# Main_ETC.net
KiCad netlist of a schematic drawn in Altium Designer
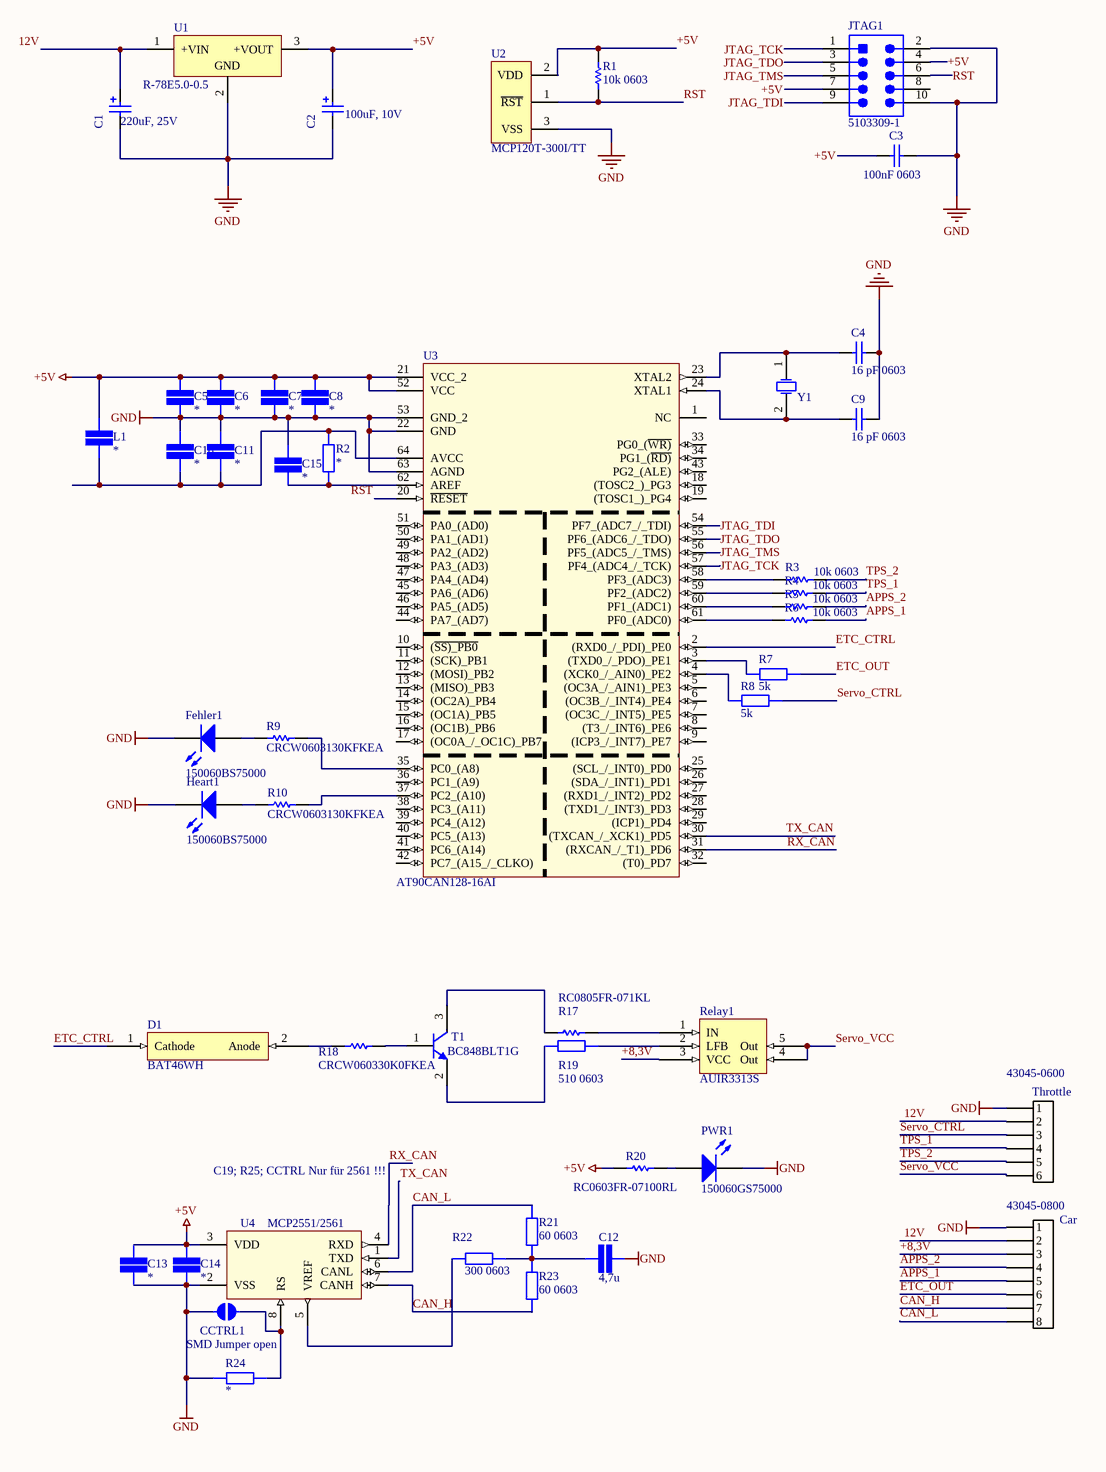
[diagram p0: Main_ETC.SchDoc]

(export (version "E")
  (design (tool "Eeschema 10.0.6"))
  (components
    (comp (ref "C1")
      (value "220uF, 25V")
      (footprint "WCAP-ATET_10x12.5")
      (description "WCAP-ATET THT Aluminum Electrolytic Capacitors, D10mm x L12.5mm, 220uF, +/-20%, 25VDC")
      (fields (field (name "PART NUMBER") "860130475006") (field (name "PUBLISHER") "Wurth Elektronik"))
      (libsource (lib "Altium_WCAP-ATET (rev19a)") (part "860130475006"))
    )
    (comp (ref "C2")
      (value "100uF, 10V")
      (footprint "WCAP-ASLU_6.3x7.7")
      (description "WCAP-ASLU Aluminium Electrolytic Capacitors, D6.3mm x L7.7mm, 100uF, +/-20%, 10VDC")
      (fields (field (name "PART NUMBER") "865090245005") (field (name "PUBLISHER") "Wurth Elektronik"))
      (libsource (lib "Altium_WCAP-ASLU (rev19a)") (part "865090245005"))
    )
    (comp (ref "C3")
      (value "100nF 0603")
      (footprint "CAPC0603(1608)100_L")
      (description "CAP 100nF 10V ±5% 0603 (1608 Metric) Thickness 1mm SMD")
      (fields (field (name "TOLERANCE") "Â±5%"))
      (libsource (lib "Altium Content Vault") (part "CAP"))
    )
    (comp (ref "C4")
      (value "16 pF 0603")
      (footprint "CAPC0603(1608)100_L")
      (description "CAP 100nF 10V ±5% 0603 (1608 Metric) Thickness 1mm SMD")
      (fields (field (name "TOLERANCE") "Â±5%"))
      (libsource (lib "Altium Content Vault") (part "CAP"))
    )
    (comp (ref "C5")
      (value "SMD Capacitor")
      (footprint "CAP 0603/1608")
      (description "Capacitor with multiple Footprints")
      (fields (field (name "ALTIUM_VALUE") "*"))
      (libsource (lib "Standardbauteile") (part "SMD Capacitor"))
    )
    (comp (ref "C6")
      (value "SMD Capacitor")
      (footprint "CAP 0603/1608")
      (description "Capacitor with multiple Footprints")
      (fields (field (name "ALTIUM_VALUE") "*"))
      (libsource (lib "Standardbauteile") (part "SMD Capacitor"))
    )
    (comp (ref "C7")
      (value "SMD Capacitor")
      (footprint "CAP 0603/1608")
      (description "Capacitor with multiple Footprints")
      (fields (field (name "ALTIUM_VALUE") "*"))
      (libsource (lib "Standardbauteile") (part "SMD Capacitor"))
    )
    (comp (ref "C8")
      (value "SMD Capacitor")
      (footprint "CAP 0603/1608")
      (description "Capacitor with multiple Footprints")
      (fields (field (name "ALTIUM_VALUE") "*"))
      (libsource (lib "Standardbauteile") (part "SMD Capacitor"))
    )
    (comp (ref "C9")
      (value "16 pF 0603")
      (footprint "CAPC0603(1608)100_L")
      (description "CAP 100nF 10V ±5% 0603 (1608 Metric) Thickness 1mm SMD")
      (fields (field (name "TOLERANCE") "Â±5%"))
      (libsource (lib "Altium Content Vault") (part "CAP"))
    )
    (comp (ref "C10")
      (value "SMD Capacitor")
      (footprint "CAP 0603/1608")
      (description "Capacitor with multiple Footprints")
      (fields (field (name "ALTIUM_VALUE") "*"))
      (libsource (lib "Standardbauteile") (part "SMD Capacitor"))
    )
    (comp (ref "C11")
      (value "SMD Capacitor")
      (footprint "CAP 0603/1608")
      (description "Capacitor with multiple Footprints")
      (fields (field (name "ALTIUM_VALUE") "*"))
      (libsource (lib "Standardbauteile") (part "SMD Capacitor"))
    )
    (comp (ref "C12")
      (value "4,7u")
      (footprint "CAP 0603/1608")
      (description "Capacitor with multiple Footprints")
      (fields (field (name "Comment") "SMD Capacitor"))
      (libsource (lib "") (part "SMD Capacitor_1"))
    )
    (comp (ref "C13")
      (value "SMD Capacitor")
      (footprint "CAP 0603/1608")
      (description "Capacitor with multiple Footprints")
      (fields (field (name "ALTIUM_VALUE") "*"))
      (libsource (lib "Standardbauteile") (part "SMD Capacitor"))
    )
    (comp (ref "C14")
      (value "SMD Capacitor")
      (footprint "CAP 0603/1608")
      (description "Capacitor with multiple Footprints")
      (fields (field (name "ALTIUM_VALUE") "*"))
      (libsource (lib "Standardbauteile") (part "SMD Capacitor"))
    )
    (comp (ref "C15")
      (value "SMD Capacitor")
      (footprint "CAP 0603/1608")
      (description "Capacitor with multiple Footprints")
      (fields (field (name "ALTIUM_VALUE") "*"))
      (libsource (lib "Standardbauteile") (part "SMD Capacitor"))
    )
    (comp (ref "Car")
      (value "43045-0800")
      (footprint "43045-0800")
      (description "Molex Micro-Fit 3.0 8-Pin\r\n600V\r\n8.5A")
      (libsource (lib "Standardbauteile") (part "MicroFit3.0 8-Pin"))
    )
    (comp (ref "CCTRL1")
      (value "SMD Jumper open")
      (footprint "SMD-JUMPER-OPEN")
      (libsource (lib "Standardbauteile") (part "SMD Jumper open"))
    )
    (comp (ref "D1")
      (value "BAT46WH")
      (footprint "DIOM2715X18N")
      (libsource (lib "Integrated_LibraryLukas") (part "BAT46WH"))
    )
    (comp (ref "Fehler1")
      (value "150060BS75000")
      (footprint "0603_A")
      (description "SMD mono-color Chip LED, WL-SMCW, Blue")
      (fields (field (name "MANUFACTURER") "Wuerth Elektronik"))
      (libsource (lib "Altium Content Vault") (part "WE-LED_K1A2-2"))
    )
    (comp (ref "Heart1")
      (value "150060BS75000")
      (footprint "0603_A")
      (description "SMD mono-color Chip LED, WL-SMCW, Blue")
      (fields (field (name "MANUFACTURER") "Wuerth Elektronik"))
      (libsource (lib "Altium Content Vault") (part "WE-LED_K1A2-2"))
    )
    (comp (ref "JTAG1")
      (value "5103309-1")
      (footprint "TECO-5103309-1_V")
      (fields (field (name "MANUFACTURER") "TE Connectivity"))
      (libsource (lib "Altium Content Vault") (part "CN-2P-M-R10"))
    )
    (comp (ref "L1")
      (value "SMD Capacitor")
      (footprint "CAP 0603/1608")
      (description "Capacitor with multiple Footprints")
      (fields (field (name "ALTIUM_VALUE") "*"))
      (libsource (lib "Standardbauteile") (part "SMD Capacitor"))
    )
    (comp (ref "PWR1")
      (value "150060GS75000")
      (footprint "0603_A")
      (description "SMD mono-color Chip LED, WL-SMCW, Green")
      (fields (field (name "MANUFACTURER") "Wuerth Elektronik"))
      (libsource (lib "Altium Content Vault") (part "WE-LED_K1A2-2"))
    )
    (comp (ref "R1")
      (value "10k 0603")
      (footprint "RESC0603(1608)_N")
      (description "127R 0.1W 1% 0603 (1608 Metric)  SMD")
      (fields (field (name "POWER") "0.1 W") (field (name "TOLERANCE") "1 %"))
      (libsource (lib "Altium Content Vault") (part "RES"))
    )
    (comp (ref "R2")
      (value "SMD Resistor")
      (footprint "STACKPOLE CSR0603")
      (description "Resistor with multiple footprints")
      (fields (field (name "ALTIUM_VALUE") "*"))
      (libsource (lib "Standardbauteile") (part "SMD Resistor"))
    )
    (comp (ref "R3")
      (value "10k 0603")
      (footprint "RESC0603(1608)_N")
      (description "127R 0.1W 1% 0603 (1608 Metric)  SMD")
      (fields (field (name "POWER") "0.1 W") (field (name "TOLERANCE") "1 %"))
      (libsource (lib "Altium Content Vault") (part "RES"))
    )
    (comp (ref "R4")
      (value "10k 0603")
      (footprint "RESC0603(1608)_N")
      (description "127R 0.1W 1% 0603 (1608 Metric)  SMD")
      (fields (field (name "POWER") "0.1 W") (field (name "TOLERANCE") "1 %"))
      (libsource (lib "Altium Content Vault") (part "RES"))
    )
    (comp (ref "R5")
      (value "10k 0603")
      (footprint "RESC0603(1608)_N")
      (description "127R 0.1W 1% 0603 (1608 Metric)  SMD")
      (fields (field (name "POWER") "0.1 W") (field (name "TOLERANCE") "1 %"))
      (libsource (lib "Altium Content Vault") (part "RES"))
    )
    (comp (ref "R6")
      (value "10k 0603")
      (footprint "RESC0603(1608)_N")
      (description "127R 0.1W 1% 0603 (1608 Metric)  SMD")
      (fields (field (name "POWER") "0.1 W") (field (name "TOLERANCE") "1 %"))
      (libsource (lib "Altium Content Vault") (part "RES"))
    )
    (comp (ref "R7")
      (value "5k")
      (footprint "STACKPOLE CSR0603")
      (description "Resistor with multiple footprints")
      (fields (field (name "Comment") "SMD Resistor"))
      (libsource (lib "Standardbauteile") (part "SMD Resistor"))
    )
    (comp (ref "R8")
      (value "5k")
      (footprint "STACKPOLE CSR0603")
      (description "Resistor with multiple footprints")
      (fields (field (name "Comment") "SMD Resistor"))
      (libsource (lib "Standardbauteile") (part "SMD Resistor"))
    )
    (comp (ref "R9")
      (value "CRCW0603130KFKEA")
      (footprint "RESC1609X50X30NL10T20")
      (fields (field (name "MANUFACTURER") "Vishay Dale"))
      (libsource (lib "Altium Content Vault") (part "RES"))
    )
    (comp (ref "R10")
      (value "CRCW0603130KFKEA")
      (footprint "RESC1609X50X30NL10T20")
      (fields (field (name "MANUFACTURER") "Vishay Dale"))
      (libsource (lib "Altium Content Vault") (part "RES"))
    )
    (comp (ref "R17")
      (value "RC0805FR-071KL")
      (footprint "RESC2013X60X35ML10T20")
      (description "Chip Resistor, 1 KOhm, +/- 1%, 125 mW, -55 to 155 degC, 0805 (2012 Metric), RoHS, Tape and Reel")
      (fields (field (name "TOLERANCE") "1%") (field (name "MANUFACTURER") "Yageo"))
      (libsource (lib "Altium Content Vault") (part "RES-2"))
    )
    (comp (ref "R18")
      (value "CRCW060330K0FKEA")
      (footprint "RESC1609X50X30LL10T20")
      (fields (field (name "MANUFACTURER") "Vishay Dale"))
      (libsource (lib "Altium Content Vault") (part "RES"))
    )
    (comp (ref "R19")
      (value "510 0603")
      (footprint "STACKPOLE CSR0603")
      (description "Resistor with multiple footprints")
      (fields (field (name "Comment") "SMD Resistor"))
      (libsource (lib "Standardbauteile") (part "SMD Resistor"))
    )
    (comp (ref "R20")
      (value "RC0603FR-07100RL")
      (footprint "RESC1608X55X25ML10T15")
      (description "Chip Resistor, 100 Ohm, +/- 1%, 0.1 W, -55 to 155 degC, 0603 (1608 Metric), RoHS, Tape and Reel")
      (fields (field (name "TOLERANCE") "1%") (field (name "MANUFACTURER") "Yageo"))
      (libsource (lib "Altium Content Vault") (part "RES-2"))
    )
    (comp (ref "R21")
      (value "60 0603")
      (footprint "STACKPOLE CSR0603")
      (description "Resistor with multiple footprints")
      (fields (field (name "Comment") "SMD Resistor"))
      (libsource (lib "Standardbauteile") (part "SMD Resistor"))
    )
    (comp (ref "R22")
      (value "300 0603")
      (footprint "STACKPOLE CSR0603")
      (description "Resistor with multiple footprints")
      (fields (field (name "Comment") "SMD Resistor"))
      (libsource (lib "Standardbauteile") (part "SMD Resistor"))
    )
    (comp (ref "R23")
      (value "60 0603")
      (footprint "STACKPOLE CSR0603")
      (description "Resistor with multiple footprints")
      (fields (field (name "Comment") "SMD Resistor"))
      (libsource (lib "Standardbauteile") (part "SMD Resistor"))
    )
    (comp (ref "R24")
      (value "SMD Resistor")
      (footprint "STACKPOLE CSR0603")
      (description "Resistor with multiple footprints")
      (fields (field (name "ALTIUM_VALUE") "*"))
      (libsource (lib "Standardbauteile") (part "SMD Resistor"))
    )
    (comp (ref "Relay1")
      (value "AUIR3313S")
      (footprint "D2PAK5 ;DPAK228P1524X483-5N")
      (libsource (lib "Integrated_LibraryLukas") (part "AUIR3313S"))
    )
    (comp (ref "T1")
      (value "BC848BLT1G")
      (footprint "ONSC-SOT-23-3-318-08_V")
      (description "General Purpose Transistor, NPN Silicon, 3-Pin SOT-23, Pb-Free, Tape and Reel")
      (fields (field (name "MANUFACTURER") "On Semiconductor"))
      (libsource (lib "Altium Content Vault") (part "ONSC-NPN-B1E2C3-3"))
    )
    (comp (ref "Throttle")
      (value "43045-0600")
      (footprint "43045-0600")
      (description "Molex Micro-Fit 3.0 6-Pin\r\n600V\r\n8.5A")
      (libsource (lib "Standardbauteile") (part "MicroFit3.0 6-Pin"))
    )
    (comp (ref "U1")
      (value "R-78E5.0-0.5")
      (footprint "REPO-R-78E-0.5-3_V")
      (description "DC/DC-Converter, 5 V Single Output, 500 mA, -40 to 85 degC, 3-Pin THD, RoHS, Tube")
      (fields (field (name "MANUFACTURER") "Recom Power"))
      (libsource (lib "Altium Content Vault") (part "REPO-R-78XX-3"))
    )
    (comp (ref "U2")
      (value "MCP120T-300I/TT")
      (footprint "SOT-23-TT3_N")
      (libsource (lib "Altium Content Vault") (part "PM-SCCT-MCP120-3"))
    )
    (comp (ref "U3")
      (value "AT90CAN128-16AI")
      (footprint "*QFP80P1600X1600X120-64N")
      (description "Ic Mcu 8bit 128kb Flash 64tqfp")
      (fields (field (name "MF") "Microchip"))
      (libsource (lib "Eric") (part "AT90CAN128-16AI"))
    )
    (comp (ref "U4")
      (value "MCP2551/2561")
      (footprint "*SOIC127P600X175-8N")
      (description "MCP2551 Series 5.5 V 1 Mb/s Surface Mount High-Speed CAN Transceiver - SOIC-8")
      (fields (field (name "MP") "MCP2551-I/SN") (field (name "MF") "Microchip"))
      (libsource (lib "Eric") (part "MCP2551-I/SN"))
    )
    (comp (ref "Y1")
      (value "16MHz, +/-30ppm, 16pF")
      (footprint "WE-XTAL_HC49/4HSMX")
      (description "WE-XTAL Quartz Crystal, size HC49-4HSMX, 16MHz, +/-30ppm, 16pF")
      (fields (field (name "PART NUMBER") "830003237") (field (name "PUBLISHER") "Wurth Elektronik"))
      (libsource (lib "Altium_WE-XTAL (rev19a)") (part "830003237"))
    )
  )
  (nets
    (net (code "1") (name "+5V") (class "Default")
      (node (ref "C13") (pin "2") (pinfunction "2_2") (pintype "passive"))
      (node (ref "C14") (pin "2") (pinfunction "2_2") (pintype "passive"))
      (node (ref "C2") (pin "2") (pinfunction "P_2") (pintype "passive"))
      (node (ref "C3") (pin "1") (pinfunction "1_1") (pintype "passive"))
      (node (ref "C5") (pin "2") (pinfunction "2_2") (pintype "passive"))
      (node (ref "C6") (pin "2") (pinfunction "2_2") (pintype "passive"))
      (node (ref "C7") (pin "2") (pinfunction "2_2") (pintype "passive"))
      (node (ref "C8") (pin "2") (pinfunction "2_2") (pintype "passive"))
      (node (ref "JTAG1") (pin "4") (pinfunction "4_4") (pintype "passive"))
      (node (ref "JTAG1") (pin "7") (pinfunction "7_7") (pintype "passive"))
      (node (ref "L1") (pin "2") (pinfunction "2_2") (pintype "passive"))
      (node (ref "R1") (pin "1") (pinfunction "1_1") (pintype "passive"))
      (node (ref "R20") (pin "1") (pinfunction "1_1") (pintype "passive"))
      (node (ref "U1") (pin "3") (pinfunction "+VOUT_3") (pintype "power_in"))
      (node (ref "U2") (pin "2") (pinfunction "VDD_2") (pintype "power_in"))
      (node (ref "U3") (pin "21") (pinfunction "VCC_2_21") (pintype "power_in"))
      (node (ref "U3") (pin "52") (pinfunction "VCC_52") (pintype "power_in"))
      (node (ref "U4") (pin "3") (pinfunction "VDD_3") (pintype "power_in"))
    )
    (net (code "2") (name "/+8,3V") (class "Default")
      (node (ref "Car") (pin "3") (pinfunction "3_3") (pintype "passive"))
      (node (ref "Relay1") (pin "3") (pinfunction "VCC_3") (pintype "input"))
    )
    (net (code "3") (name "/12V") (class "Default")
      (node (ref "C1") (pin "2") (pinfunction "P_2") (pintype "passive"))
      (node (ref "Car") (pin "2") (pinfunction "2_2") (pintype "passive"))
      (node (ref "Throttle") (pin "2") (pinfunction "2_2") (pintype "passive"))
      (node (ref "U1") (pin "1") (pinfunction "+VIN_1") (pintype "power_in"))
    )
    (net (code "4") (name "/APPS_1") (class "Default")
      (node (ref "Car") (pin "5") (pinfunction "5_5") (pintype "passive"))
      (node (ref "R6") (pin "1") (pinfunction "1_1") (pintype "passive"))
    )
    (net (code "5") (name "/APPS_2") (class "Default")
      (node (ref "Car") (pin "4") (pinfunction "4_4") (pintype "passive"))
      (node (ref "R5") (pin "1") (pinfunction "1_1") (pintype "passive"))
    )
    (net (code "6") (name "/CAN_H") (class "Default")
      (node (ref "Car") (pin "7") (pinfunction "7_7") (pintype "passive"))
      (node (ref "R23") (pin "2") (pinfunction "2_2") (pintype "passive"))
      (node (ref "U4") (pin "7") (pinfunction "CANH_7") (pintype "bidirectional"))
    )
    (net (code "7") (name "/CAN_L") (class "Default")
      (node (ref "Car") (pin "8") (pinfunction "8_8") (pintype "passive"))
      (node (ref "R21") (pin "1") (pinfunction "1_1") (pintype "passive"))
      (node (ref "U4") (pin "6") (pinfunction "CANL_6") (pintype "bidirectional"))
    )
    (net (code "8") (name "/ETC_CTRL") (class "Default")
      (node (ref "D1") (pin "1") (pinfunction "Cathode_1") (pintype "input"))
      (node (ref "U3") (pin "2") (pinfunction "(RXD0_/_PDI)_PE0_2") (pintype "bidirectional"))
    )
    (net (code "9") (name "/ETC_OUT") (class "Default")
      (node (ref "Car") (pin "6") (pinfunction "6_6") (pintype "passive"))
      (node (ref "R7") (pin "1") (pinfunction "1_1") (pintype "passive"))
    )
    (net (code "10") (name "/JTAG_TCK") (class "Default")
      (node (ref "JTAG1") (pin "1") (pinfunction "1_1") (pintype "passive"))
      (node (ref "U3") (pin "57") (pinfunction "PF4_(ADC4_/_TCK)_57") (pintype "bidirectional"))
    )
    (net (code "11") (name "/JTAG_TDI") (class "Default")
      (node (ref "JTAG1") (pin "9") (pinfunction "9_9") (pintype "passive"))
      (node (ref "U3") (pin "54") (pinfunction "PF7_(ADC7_/_TDI)_54") (pintype "bidirectional"))
    )
    (net (code "12") (name "/JTAG_TDO") (class "Default")
      (node (ref "JTAG1") (pin "3") (pinfunction "3_3") (pintype "passive"))
      (node (ref "U3") (pin "55") (pinfunction "PF6_(ADC6_/_TDO)_55") (pintype "bidirectional"))
    )
    (net (code "13") (name "/JTAG_TMS") (class "Default")
      (node (ref "JTAG1") (pin "5") (pinfunction "5_5") (pintype "passive"))
      (node (ref "U3") (pin "56") (pinfunction "PF5_(ADC5_/_TMS)_56") (pintype "bidirectional"))
    )
    (net (code "14") (name "/RST") (class "Default")
      (node (ref "JTAG1") (pin "6") (pinfunction "6_6") (pintype "passive"))
      (node (ref "R1") (pin "2") (pinfunction "2_2") (pintype "passive"))
      (node (ref "U2") (pin "1") (pinfunction "~{RST}_1") (pintype "open_collector"))
      (node (ref "U3") (pin "20") (pinfunction "~{RESET}_20") (pintype "input"))
    )
    (net (code "15") (name "/RX_CAN") (class "Default")
      (node (ref "U3") (pin "31") (pinfunction "(RXCAN_/_T1)_PD6_31") (pintype "bidirectional"))
      (node (ref "U4") (pin "4") (pinfunction "RXD_4") (pintype "output"))
    )
    (net (code "16") (name "/Servo_CTRL") (class "Default")
      (node (ref "R8") (pin "1") (pinfunction "1_1") (pintype "passive"))
      (node (ref "Throttle") (pin "3") (pinfunction "3_3") (pintype "passive"))
    )
    (net (code "17") (name "/Servo_VCC") (class "Default")
      (node (ref "Relay1") (pin "4") (pinfunction "Out_4") (pintype "input"))
      (node (ref "Relay1") (pin "5") (pinfunction "Out_5") (pintype "input"))
      (node (ref "Throttle") (pin "6") (pinfunction "6_6") (pintype "passive"))
    )
    (net (code "18") (name "/TPS_1") (class "Default")
      (node (ref "R4") (pin "1") (pinfunction "1_1") (pintype "passive"))
      (node (ref "Throttle") (pin "4") (pinfunction "4_4") (pintype "passive"))
    )
    (net (code "19") (name "/TPS_2") (class "Default")
      (node (ref "R3") (pin "1") (pinfunction "1_1") (pintype "passive"))
      (node (ref "Throttle") (pin "5") (pinfunction "5_5") (pintype "passive"))
    )
    (net (code "20") (name "/TX_CAN") (class "Default")
      (node (ref "U3") (pin "30") (pinfunction "(TXCAN_/_XCK1)_PD5_30") (pintype "bidirectional"))
      (node (ref "U4") (pin "1") (pinfunction "TXD_1") (pintype "input"))
    )
    (net (code "21") (name "GND") (class "Default")
      (node (ref "C1") (pin "1") (pinfunction "N_1") (pintype "passive"))
      (node (ref "C10") (pin "2") (pinfunction "2_2") (pintype "passive"))
      (node (ref "C11") (pin "2") (pinfunction "2_2") (pintype "passive"))
      (node (ref "C13") (pin "1") (pinfunction "1_1") (pintype "passive"))
      (node (ref "C14") (pin "1") (pinfunction "1_1") (pintype "passive"))
      (node (ref "C15") (pin "2") (pinfunction "2_2") (pintype "passive"))
      (node (ref "C2") (pin "1") (pinfunction "N_1") (pintype "passive"))
      (node (ref "C3") (pin "2") (pinfunction "2_2") (pintype "passive"))
      (node (ref "C4") (pin "2") (pinfunction "2_2") (pintype "passive"))
      (node (ref "C5") (pin "1") (pinfunction "1_1") (pintype "passive"))
      (node (ref "C6") (pin "1") (pinfunction "1_1") (pintype "passive"))
      (node (ref "C7") (pin "1") (pinfunction "1_1") (pintype "passive"))
      (node (ref "C8") (pin "1") (pinfunction "1_1") (pintype "passive"))
      (node (ref "C9") (pin "2") (pinfunction "2_2") (pintype "passive"))
      (node (ref "CCTRL1") (pin "1") (pinfunction "1_1") (pintype "passive"))
      (node (ref "Car") (pin "1") (pinfunction "1_1") (pintype "passive"))
      (node (ref "Fehler1") (pin "1") (pinfunction "K_1") (pintype "passive"))
      (node (ref "Heart1") (pin "1") (pinfunction "K_1") (pintype "passive"))
      (node (ref "JTAG1") (pin "10") (pinfunction "10_10") (pintype "passive"))
      (node (ref "JTAG1") (pin "2") (pinfunction "2_2") (pintype "passive"))
      (node (ref "PWR1") (pin "1") (pinfunction "K_1") (pintype "passive"))
      (node (ref "R24") (pin "1") (pinfunction "1_1") (pintype "passive"))
      (node (ref "Throttle") (pin "1") (pinfunction "1_1") (pintype "passive"))
      (node (ref "U1") (pin "2") (pinfunction "GND_2") (pintype "power_in"))
      (node (ref "U2") (pin "3") (pinfunction "VSS_3") (pintype "power_in"))
      (node (ref "U3") (pin "22") (pinfunction "GND_22") (pintype "passive"))
      (node (ref "U3") (pin "53") (pinfunction "GND_2_53") (pintype "passive"))
      (node (ref "U3") (pin "63") (pinfunction "AGND_63") (pintype "passive"))
      (node (ref "U4") (pin "2") (pinfunction "VSS_2") (pintype "passive"))
    )
    (net (code "22") (name "Net-(C12-Pad1)") (class "Default")
      (node (ref "C12") (pin "1") (pinfunction "1_1") (pintype "passive"))
      (node (ref "R21") (pin "2") (pinfunction "2_2") (pintype "passive"))
      (node (ref "R22") (pin "2") (pinfunction "2_2") (pintype "passive"))
      (node (ref "R23") (pin "1") (pinfunction "1_1") (pintype "passive"))
    )
    (net (code "23") (name "Net-(D1-Anode)") (class "Default")
      (node (ref "D1") (pin "2") (pinfunction "Anode_2") (pintype "input"))
      (node (ref "R18") (pin "1") (pinfunction "1_1") (pintype "passive"))
    )
    (net (code "24") (name "Net-(Fehler1-A)") (class "Default")
      (node (ref "Fehler1") (pin "2") (pinfunction "A_2") (pintype "passive"))
      (node (ref "R9") (pin "2") (pinfunction "2_2") (pintype "passive"))
    )
    (net (code "25") (name "Net-(Heart1-A)") (class "Default")
      (node (ref "Heart1") (pin "2") (pinfunction "A_2") (pintype "passive"))
      (node (ref "R10") (pin "2") (pinfunction "2_2") (pintype "passive"))
    )
    (net (code "26") (name "Net-(PWR1-A)") (class "Default")
      (node (ref "PWR1") (pin "2") (pinfunction "A_2") (pintype "passive"))
      (node (ref "R20") (pin "2") (pinfunction "2_2") (pintype "passive"))
    )
    (net (code "27") (name "Net-(Relay1-IN)") (class "Default")
      (node (ref "R17") (pin "2") (pinfunction "2_2") (pintype "passive"))
      (node (ref "Relay1") (pin "1") (pinfunction "IN_1") (pintype "input"))
    )
    (net (code "28") (name "Net-(Relay1-LFB)") (class "Default")
      (node (ref "R19") (pin "2") (pinfunction "2_2") (pintype "passive"))
      (node (ref "Relay1") (pin "2") (pinfunction "LFB_2") (pintype "input"))
    )
    (net (code "29") (name "Net-(T1-B)") (class "Default")
      (node (ref "R18") (pin "2") (pinfunction "2_2") (pintype "passive"))
      (node (ref "T1") (pin "1") (pinfunction "B_1") (pintype "passive"))
    )
    (net (code "30") (name "Net-(T1-C)") (class "Default")
      (node (ref "R17") (pin "1") (pinfunction "1_1") (pintype "passive"))
      (node (ref "T1") (pin "3") (pinfunction "C_3") (pintype "passive"))
    )
    (net (code "31") (name "Net-(T1-E)") (class "Default")
      (node (ref "R19") (pin "1") (pinfunction "1_1") (pintype "passive"))
      (node (ref "T1") (pin "2") (pinfunction "E_2") (pintype "passive"))
    )
    (net (code "32") (name "Net-(U3-(TXD0_{slash}_PDO)_PE1)") (class "Default")
      (node (ref "R7") (pin "2") (pinfunction "2_2") (pintype "passive"))
      (node (ref "U3") (pin "3") (pinfunction "(TXD0_/_PDO)_PE1_3") (pintype "bidirectional"))
    )
    (net (code "33") (name "Net-(U3-(XCK0_{slash}_AIN0)_PE2)") (class "Default")
      (node (ref "R8") (pin "2") (pinfunction "2_2") (pintype "passive"))
      (node (ref "U3") (pin "4") (pinfunction "(XCK0_/_AIN0)_PE2_4") (pintype "bidirectional"))
    )
    (net (code "34") (name "Net-(U3-AREF)") (class "Default")
      (node (ref "C15") (pin "1") (pinfunction "1_1") (pintype "passive"))
      (node (ref "R2") (pin "1") (pinfunction "1_1") (pintype "passive"))
      (node (ref "U3") (pin "62") (pinfunction "AREF_62") (pintype "input"))
    )
    (net (code "35") (name "Net-(U3-AVCC)") (class "Default")
      (node (ref "C10") (pin "1") (pinfunction "1_1") (pintype "passive"))
      (node (ref "C11") (pin "1") (pinfunction "1_1") (pintype "passive"))
      (node (ref "L1") (pin "1") (pinfunction "1_1") (pintype "passive"))
      (node (ref "R2") (pin "2") (pinfunction "2_2") (pintype "passive"))
      (node (ref "U3") (pin "64") (pinfunction "AVCC_64") (pintype "power_in"))
    )
    (net (code "36") (name "Net-(U3-PC0_(A8))") (class "Default")
      (node (ref "R9") (pin "1") (pinfunction "1_1") (pintype "passive"))
      (node (ref "U3") (pin "35") (pinfunction "PC0_(A8)_35") (pintype "bidirectional"))
    )
    (net (code "37") (name "Net-(U3-PC2_(A10))") (class "Default")
      (node (ref "R10") (pin "1") (pinfunction "1_1") (pintype "passive"))
      (node (ref "U3") (pin "37") (pinfunction "PC2_(A10)_37") (pintype "bidirectional"))
    )
    (net (code "38") (name "Net-(U3-PF0_(ADC0))") (class "Default")
      (node (ref "R6") (pin "2") (pinfunction "2_2") (pintype "passive"))
      (node (ref "U3") (pin "61") (pinfunction "PF0_(ADC0)_61") (pintype "bidirectional"))
    )
    (net (code "39") (name "Net-(U3-PF1_(ADC1))") (class "Default")
      (node (ref "R5") (pin "2") (pinfunction "2_2") (pintype "passive"))
      (node (ref "U3") (pin "60") (pinfunction "PF1_(ADC1)_60") (pintype "bidirectional"))
    )
    (net (code "40") (name "Net-(U3-PF2_(ADC2))") (class "Default")
      (node (ref "R4") (pin "2") (pinfunction "2_2") (pintype "passive"))
      (node (ref "U3") (pin "59") (pinfunction "PF2_(ADC2)_59") (pintype "bidirectional"))
    )
    (net (code "41") (name "Net-(U3-PF3_(ADC3))") (class "Default")
      (node (ref "R3") (pin "2") (pinfunction "2_2") (pintype "passive"))
      (node (ref "U3") (pin "58") (pinfunction "PF3_(ADC3)_58") (pintype "bidirectional"))
    )
    (net (code "42") (name "Net-(U3-XTAL1)") (class "Default")
      (node (ref "C9") (pin "1") (pinfunction "1_1") (pintype "passive"))
      (node (ref "U3") (pin "24") (pinfunction "XTAL1_24") (pintype "input"))
      (node (ref "Y1") (pin "2") (pinfunction "OSC2_2") (pintype "passive"))
    )
    (net (code "43") (name "Net-(U3-XTAL2)") (class "Default")
      (node (ref "C4") (pin "1") (pinfunction "1_1") (pintype "passive"))
      (node (ref "U3") (pin "23") (pinfunction "XTAL2_23") (pintype "output"))
      (node (ref "Y1") (pin "1") (pinfunction "OSC1_1") (pintype "passive"))
    )
    (net (code "44") (name "Net-(U4-RS)") (class "Default")
      (node (ref "CCTRL1") (pin "2") (pinfunction "2_2") (pintype "passive"))
      (node (ref "R24") (pin "2") (pinfunction "2_2") (pintype "passive"))
      (node (ref "U4") (pin "8") (pinfunction "RS_8") (pintype "input"))
    )
    (net (code "45") (name "Net-(U4-VREF)") (class "Default")
      (node (ref "R22") (pin "1") (pinfunction "1_1") (pintype "passive"))
      (node (ref "U4") (pin "5") (pinfunction "VREF_5") (pintype "output"))
    )
    (net (code "46") (name "unconnected-(C12-Pad2)") (class "Default")
      (node (ref "C12") (pin "2") (pinfunction "2_2") (pintype "passive"))
    )
    (net (code "47") (name "unconnected-(JTAG1-Pad8)") (class "Default")
      (node (ref "JTAG1") (pin "8") (pinfunction "8_8") (pintype "passive"))
    )
    (net (code "48") (name "unconnected-(U3-(ICP1)_PD4-Pad29)") (class "Default")
      (node (ref "U3") (pin "29") (pinfunction "(ICP1)_PD4_29") (pintype "bidirectional"))
    )
    (net (code "49") (name "unconnected-(U3-(ICP3_{slash}_INT7)_PE7-Pad9)") (class "Default")
      (node (ref "U3") (pin "9") (pinfunction "(ICP3_/_INT7)_PE7_9") (pintype "bidirectional"))
    )
    (net (code "50") (name "unconnected-(U3-(MISO)_PB3-Pad13)") (class "Default")
      (node (ref "U3") (pin "13") (pinfunction "(MISO)_PB3_13") (pintype "bidirectional"))
    )
    (net (code "51") (name "unconnected-(U3-(MOSI)_PB2-Pad12)") (class "Default")
      (node (ref "U3") (pin "12") (pinfunction "(MOSI)_PB2_12") (pintype "bidirectional"))
    )
    (net (code "52") (name "unconnected-(U3-(OC0A_{slash}_OC1C)_PB7-Pad17)") (class "Default")
      (node (ref "U3") (pin "17") (pinfunction "(OC0A_/_OC1C)_PB7_17") (pintype "bidirectional"))
    )
    (net (code "53") (name "unconnected-(U3-(OC1A)_PB5-Pad15)") (class "Default")
      (node (ref "U3") (pin "15") (pinfunction "(OC1A)_PB5_15") (pintype "bidirectional"))
    )
    (net (code "54") (name "unconnected-(U3-(OC1B)_PB6-Pad16)") (class "Default")
      (node (ref "U3") (pin "16") (pinfunction "(OC1B)_PB6_16") (pintype "bidirectional"))
    )
    (net (code "55") (name "unconnected-(U3-(OC2A)_PB4-Pad14)") (class "Default")
      (node (ref "U3") (pin "14") (pinfunction "(OC2A)_PB4_14") (pintype "bidirectional"))
    )
    (net (code "56") (name "unconnected-(U3-(OC3A_{slash}_AIN1)_PE3-Pad5)") (class "Default")
      (node (ref "U3") (pin "5") (pinfunction "(OC3A_/_AIN1)_PE3_5") (pintype "bidirectional"))
    )
    (net (code "57") (name "unconnected-(U3-(OC3B_{slash}_INT4)_PE4-Pad6)") (class "Default")
      (node (ref "U3") (pin "6") (pinfunction "(OC3B_/_INT4)_PE4_6") (pintype "bidirectional"))
    )
    (net (code "58") (name "unconnected-(U3-(OC3C_{slash}_INT5)_PE5-Pad7)") (class "Default")
      (node (ref "U3") (pin "7") (pinfunction "(OC3C_/_INT5)_PE5_7") (pintype "bidirectional"))
    )
    (net (code "59") (name "unconnected-(U3-(RXD1_{slash}_INT2)_PD2-Pad27)") (class "Default")
      (node (ref "U3") (pin "27") (pinfunction "(RXD1_/_INT2)_PD2_27") (pintype "bidirectional"))
    )
    (net (code "60") (name "unconnected-(U3-(SCK)_PB1-Pad11)") (class "Default")
      (node (ref "U3") (pin "11") (pinfunction "(SCK)_PB1_11") (pintype "bidirectional"))
    )
    (net (code "61") (name "unconnected-(U3-(SCL_{slash}_INT0)_PD0-Pad25)") (class "Default")
      (node (ref "U3") (pin "25") (pinfunction "(SCL_/_INT0)_PD0_25") (pintype "bidirectional"))
    )
    (net (code "62") (name "unconnected-(U3-(SDA_{slash}_INT1)_PD1-Pad26)") (class "Default")
      (node (ref "U3") (pin "26") (pinfunction "(SDA_/_INT1)_PD1_26") (pintype "bidirectional"))
    )
    (net (code "63") (name "unconnected-(U3-(T0)_PD7-Pad32)") (class "Default")
      (node (ref "U3") (pin "32") (pinfunction "(T0)_PD7_32") (pintype "bidirectional"))
    )
    (net (code "64") (name "unconnected-(U3-(T3_{slash}_INT6)_PE6-Pad8)") (class "Default")
      (node (ref "U3") (pin "8") (pinfunction "(T3_/_INT6)_PE6_8") (pintype "bidirectional"))
    )
    (net (code "65") (name "unconnected-(U3-(TOSC1_)_PG4-Pad19)") (class "Default")
      (node (ref "U3") (pin "19") (pinfunction "(TOSC1_)_PG4_19") (pintype "bidirectional"))
    )
    (net (code "66") (name "unconnected-(U3-(TOSC2_)_PG3-Pad18)") (class "Default")
      (node (ref "U3") (pin "18") (pinfunction "(TOSC2_)_PG3_18") (pintype "bidirectional"))
    )
    (net (code "67") (name "unconnected-(U3-(TXD1_{slash}_INT3)_PD3-Pad28)") (class "Default")
      (node (ref "U3") (pin "28") (pinfunction "(TXD1_/_INT3)_PD3_28") (pintype "bidirectional"))
    )
    (net (code "68") (name "unconnected-(U3-(~{SS)_PB0}-Pad10)") (class "Default")
      (node (ref "U3") (pin "10") (pinfunction "(~{SS)_PB0}_10") (pintype "bidirectional"))
    )
    (net (code "69") (name "unconnected-(U3-NC-Pad1)") (class "Default")
      (node (ref "U3") (pin "1") (pinfunction "NC_1") (pintype "passive"))
    )
    (net (code "70") (name "unconnected-(U3-PA0_(AD0)-Pad51)") (class "Default")
      (node (ref "U3") (pin "51") (pinfunction "PA0_(AD0)_51") (pintype "bidirectional"))
    )
    (net (code "71") (name "unconnected-(U3-PA1_(AD1)-Pad50)") (class "Default")
      (node (ref "U3") (pin "50") (pinfunction "PA1_(AD1)_50") (pintype "bidirectional"))
    )
    (net (code "72") (name "unconnected-(U3-PA2_(AD2)-Pad49)") (class "Default")
      (node (ref "U3") (pin "49") (pinfunction "PA2_(AD2)_49") (pintype "bidirectional"))
    )
    (net (code "73") (name "unconnected-(U3-PA3_(AD3)-Pad48)") (class "Default")
      (node (ref "U3") (pin "48") (pinfunction "PA3_(AD3)_48") (pintype "bidirectional"))
    )
    (net (code "74") (name "unconnected-(U3-PA4_(AD4)-Pad47)") (class "Default")
      (node (ref "U3") (pin "47") (pinfunction "PA4_(AD4)_47") (pintype "bidirectional"))
    )
    (net (code "75") (name "unconnected-(U3-PA5_(AD5)-Pad46)") (class "Default")
      (node (ref "U3") (pin "46") (pinfunction "PA5_(AD5)_46") (pintype "bidirectional"))
    )
    (net (code "76") (name "unconnected-(U3-PA6_(AD6)-Pad45)") (class "Default")
      (node (ref "U3") (pin "45") (pinfunction "PA6_(AD6)_45") (pintype "bidirectional"))
    )
    (net (code "77") (name "unconnected-(U3-PA7_(AD7)-Pad44)") (class "Default")
      (node (ref "U3") (pin "44") (pinfunction "PA7_(AD7)_44") (pintype "bidirectional"))
    )
    (net (code "78") (name "unconnected-(U3-PC1_(A9)-Pad36)") (class "Default")
      (node (ref "U3") (pin "36") (pinfunction "PC1_(A9)_36") (pintype "bidirectional"))
    )
    (net (code "79") (name "unconnected-(U3-PC3_(A11)-Pad38)") (class "Default")
      (node (ref "U3") (pin "38") (pinfunction "PC3_(A11)_38") (pintype "bidirectional"))
    )
    (net (code "80") (name "unconnected-(U3-PC4_(A12)-Pad39)") (class "Default")
      (node (ref "U3") (pin "39") (pinfunction "PC4_(A12)_39") (pintype "bidirectional"))
    )
    (net (code "81") (name "unconnected-(U3-PC5_(A13)-Pad40)") (class "Default")
      (node (ref "U3") (pin "40") (pinfunction "PC5_(A13)_40") (pintype "bidirectional"))
    )
    (net (code "82") (name "unconnected-(U3-PC6_(A14)-Pad41)") (class "Default")
      (node (ref "U3") (pin "41") (pinfunction "PC6_(A14)_41") (pintype "bidirectional"))
    )
    (net (code "83") (name "unconnected-(U3-PC7_(A15_{slash}_CLKO)-Pad42)") (class "Default")
      (node (ref "U3") (pin "42") (pinfunction "PC7_(A15_/_CLKO)_42") (pintype "bidirectional"))
    )
    (net (code "84") (name "unconnected-(U3-PG0_(~{WR)}-Pad33)") (class "Default")
      (node (ref "U3") (pin "33") (pinfunction "PG0_(~{WR)}_33") (pintype "bidirectional"))
    )
    (net (code "85") (name "unconnected-(U3-PG1_(~{RD)}-Pad34)") (class "Default")
      (node (ref "U3") (pin "34") (pinfunction "PG1_(~{RD)}_34") (pintype "bidirectional"))
    )
    (net (code "86") (name "unconnected-(U3-PG2_(ALE)-Pad43)") (class "Default")
      (node (ref "U3") (pin "43") (pinfunction "PG2_(ALE)_43") (pintype "bidirectional"))
    )
  )
)
